# Accumulator_HotDog_v2.net
KiCad netlist of a schematic drawn in Altium Designer
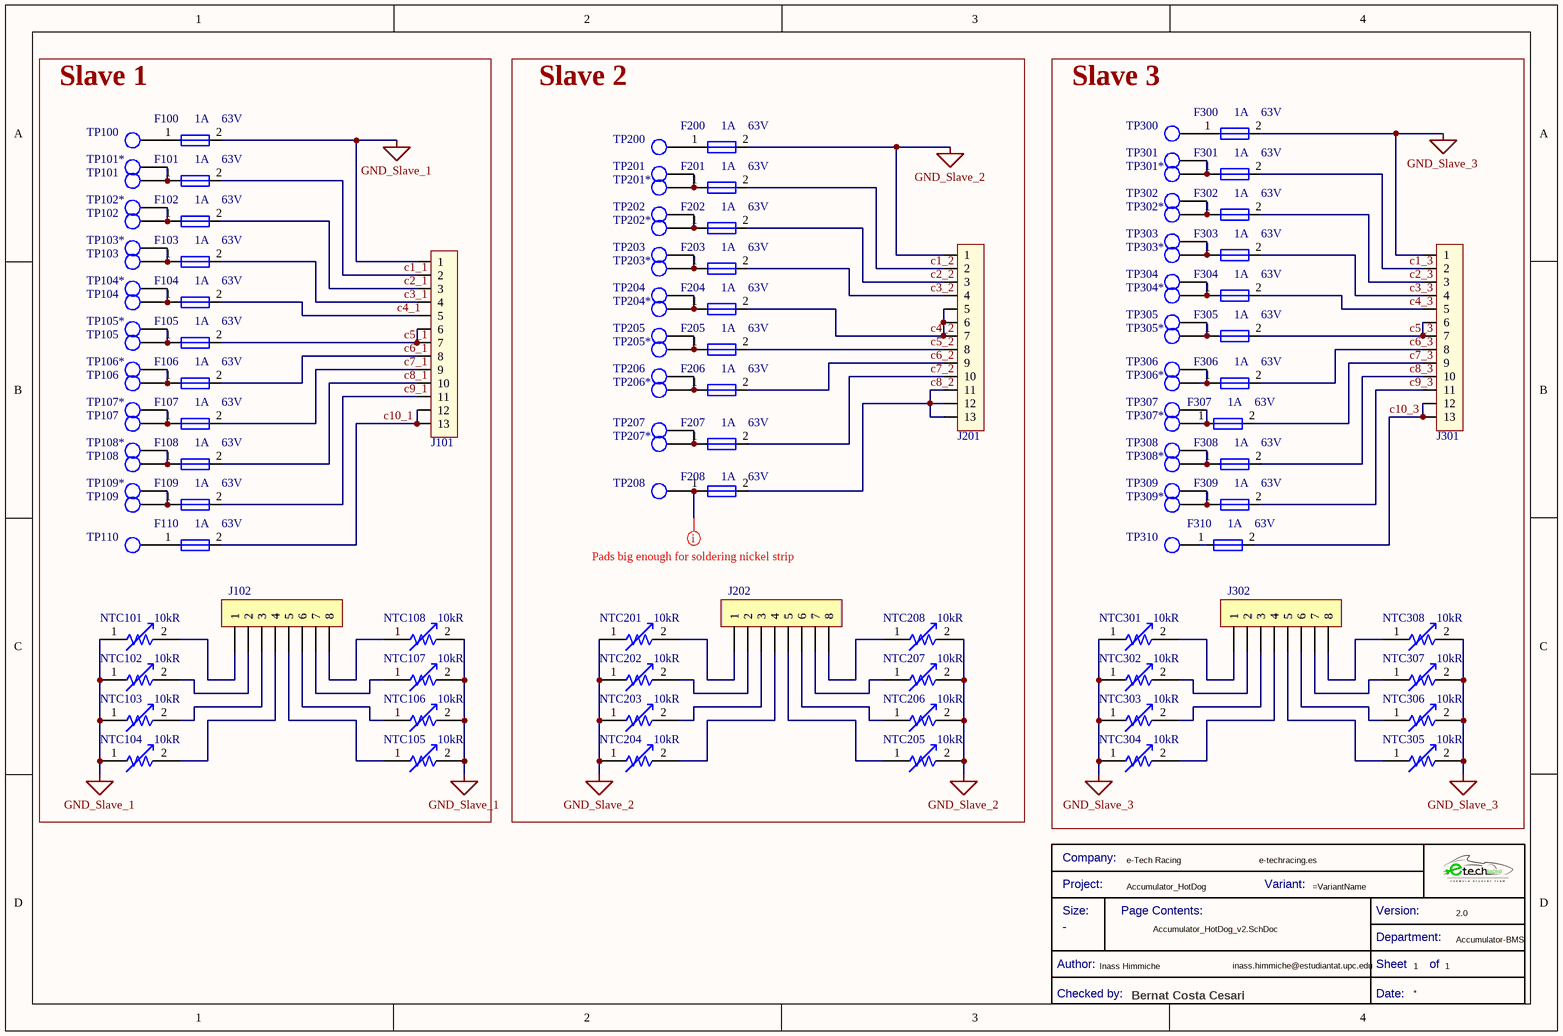
[diagram p0: Accumulator_HotDog_v2.SchDoc]

(export (version "E")
  (design (tool "Eeschema 10.0.6"))
  (components
    (comp (ref "*")
      (value "Title Block_template")
      (description "Standard Title Block")
      (fields (field (name "SIZE") "-"))
      (libsource (lib "e-Tech_Racing") (part "Title Block_template"))
    )
    (comp (ref "F100")
      (value "0437001.WRA")
      (footprint "Fuse_1206")
      (description "Fuse Chip Fast Acting 1A 63V SMD Solder Pad 1206 Ceramic T/R Automotive")
      (fields
        (field (name "MANUFACTURER") "Littelfuse")
        (field (name "CURRENT RATING") "1A")
        (field (name "VOLTAGE RATING (DC)") "63V")
      )
      (libsource (lib "Filter components") (part "Fuse_1A_63V_1206"))
    )
    (comp (ref "F101")
      (value "0437001.WRA")
      (footprint "Fuse_1206")
      (description "Fuse Chip Fast Acting 1A 63V SMD Solder Pad 1206 Ceramic T/R Automotive")
      (fields
        (field (name "MANUFACTURER") "Littelfuse")
        (field (name "CURRENT RATING") "1A")
        (field (name "VOLTAGE RATING (DC)") "63V")
      )
      (libsource (lib "Filter components") (part "Fuse_1A_63V_1206"))
    )
    (comp (ref "F102")
      (value "0437001.WRA")
      (footprint "Fuse_1206")
      (description "Fuse Chip Fast Acting 1A 63V SMD Solder Pad 1206 Ceramic T/R Automotive")
      (fields
        (field (name "MANUFACTURER") "Littelfuse")
        (field (name "CURRENT RATING") "1A")
        (field (name "VOLTAGE RATING (DC)") "63V")
      )
      (libsource (lib "Filter components") (part "Fuse_1A_63V_1206"))
    )
    (comp (ref "F103")
      (value "0437001.WRA")
      (footprint "Fuse_1206")
      (description "Fuse Chip Fast Acting 1A 63V SMD Solder Pad 1206 Ceramic T/R Automotive")
      (fields
        (field (name "MANUFACTURER") "Littelfuse")
        (field (name "CURRENT RATING") "1A")
        (field (name "VOLTAGE RATING (DC)") "63V")
      )
      (libsource (lib "Filter components") (part "Fuse_1A_63V_1206"))
    )
    (comp (ref "F104")
      (value "0437001.WRA")
      (footprint "Fuse_1206")
      (description "Fuse Chip Fast Acting 1A 63V SMD Solder Pad 1206 Ceramic T/R Automotive")
      (fields
        (field (name "MANUFACTURER") "Littelfuse")
        (field (name "CURRENT RATING") "1A")
        (field (name "VOLTAGE RATING (DC)") "63V")
      )
      (libsource (lib "Filter components") (part "Fuse_1A_63V_1206"))
    )
    (comp (ref "F105")
      (value "0437001.WRA")
      (footprint "Fuse_1206")
      (description "Fuse Chip Fast Acting 1A 63V SMD Solder Pad 1206 Ceramic T/R Automotive")
      (fields
        (field (name "MANUFACTURER") "Littelfuse")
        (field (name "CURRENT RATING") "1A")
        (field (name "VOLTAGE RATING (DC)") "63V")
      )
      (libsource (lib "Filter components") (part "Fuse_1A_63V_1206"))
    )
    (comp (ref "F106")
      (value "0437001.WRA")
      (footprint "Fuse_1206")
      (description "Fuse Chip Fast Acting 1A 63V SMD Solder Pad 1206 Ceramic T/R Automotive")
      (fields
        (field (name "MANUFACTURER") "Littelfuse")
        (field (name "CURRENT RATING") "1A")
        (field (name "VOLTAGE RATING (DC)") "63V")
      )
      (libsource (lib "Filter components") (part "Fuse_1A_63V_1206"))
    )
    (comp (ref "F107")
      (value "0437001.WRA")
      (footprint "Fuse_1206")
      (description "Fuse Chip Fast Acting 1A 63V SMD Solder Pad 1206 Ceramic T/R Automotive")
      (fields
        (field (name "MANUFACTURER") "Littelfuse")
        (field (name "CURRENT RATING") "1A")
        (field (name "VOLTAGE RATING (DC)") "63V")
      )
      (libsource (lib "Filter components") (part "Fuse_1A_63V_1206"))
    )
    (comp (ref "F108")
      (value "0437001.WRA")
      (footprint "Fuse_1206")
      (description "Fuse Chip Fast Acting 1A 63V SMD Solder Pad 1206 Ceramic T/R Automotive")
      (fields
        (field (name "MANUFACTURER") "Littelfuse")
        (field (name "CURRENT RATING") "1A")
        (field (name "VOLTAGE RATING (DC)") "63V")
      )
      (libsource (lib "Filter components") (part "Fuse_1A_63V_1206"))
    )
    (comp (ref "F109")
      (value "0437001.WRA")
      (footprint "Fuse_1206")
      (description "Fuse Chip Fast Acting 1A 63V SMD Solder Pad 1206 Ceramic T/R Automotive")
      (fields
        (field (name "MANUFACTURER") "Littelfuse")
        (field (name "CURRENT RATING") "1A")
        (field (name "VOLTAGE RATING (DC)") "63V")
      )
      (libsource (lib "Filter components") (part "Fuse_1A_63V_1206"))
    )
    (comp (ref "F110")
      (value "0437001.WRA")
      (footprint "Fuse_1206")
      (description "Fuse Chip Fast Acting 1A 63V SMD Solder Pad 1206 Ceramic T/R Automotive")
      (fields
        (field (name "MANUFACTURER") "Littelfuse")
        (field (name "CURRENT RATING") "1A")
        (field (name "VOLTAGE RATING (DC)") "63V")
      )
      (libsource (lib "Filter components") (part "Fuse_1A_63V_1206"))
    )
    (comp (ref "F200")
      (value "0437001.WRA")
      (footprint "Fuse_1206")
      (description "Fuse Chip Fast Acting 1A 63V SMD Solder Pad 1206 Ceramic T/R Automotive")
      (fields
        (field (name "MANUFACTURER") "Littelfuse")
        (field (name "CURRENT RATING") "1A")
        (field (name "VOLTAGE RATING (DC)") "63V")
      )
      (libsource (lib "Filter components") (part "Fuse_1A_63V_1206"))
    )
    (comp (ref "F201")
      (value "0437001.WRA")
      (footprint "Fuse_1206")
      (description "Fuse Chip Fast Acting 1A 63V SMD Solder Pad 1206 Ceramic T/R Automotive")
      (fields
        (field (name "MANUFACTURER") "Littelfuse")
        (field (name "CURRENT RATING") "1A")
        (field (name "VOLTAGE RATING (DC)") "63V")
      )
      (libsource (lib "Filter components") (part "Fuse_1A_63V_1206"))
    )
    (comp (ref "F202")
      (value "0437001.WRA")
      (footprint "Fuse_1206")
      (description "Fuse Chip Fast Acting 1A 63V SMD Solder Pad 1206 Ceramic T/R Automotive")
      (fields
        (field (name "MANUFACTURER") "Littelfuse")
        (field (name "CURRENT RATING") "1A")
        (field (name "VOLTAGE RATING (DC)") "63V")
      )
      (libsource (lib "Filter components") (part "Fuse_1A_63V_1206"))
    )
    (comp (ref "F203")
      (value "0437001.WRA")
      (footprint "Fuse_1206")
      (description "Fuse Chip Fast Acting 1A 63V SMD Solder Pad 1206 Ceramic T/R Automotive")
      (fields
        (field (name "MANUFACTURER") "Littelfuse")
        (field (name "CURRENT RATING") "1A")
        (field (name "VOLTAGE RATING (DC)") "63V")
      )
      (libsource (lib "Filter components") (part "Fuse_1A_63V_1206"))
    )
    (comp (ref "F204")
      (value "0437001.WRA")
      (footprint "Fuse_1206")
      (description "Fuse Chip Fast Acting 1A 63V SMD Solder Pad 1206 Ceramic T/R Automotive")
      (fields
        (field (name "MANUFACTURER") "Littelfuse")
        (field (name "CURRENT RATING") "1A")
        (field (name "VOLTAGE RATING (DC)") "63V")
      )
      (libsource (lib "Filter components") (part "Fuse_1A_63V_1206"))
    )
    (comp (ref "F205")
      (value "0437001.WRA")
      (footprint "Fuse_1206")
      (description "Fuse Chip Fast Acting 1A 63V SMD Solder Pad 1206 Ceramic T/R Automotive")
      (fields
        (field (name "MANUFACTURER") "Littelfuse")
        (field (name "CURRENT RATING") "1A")
        (field (name "VOLTAGE RATING (DC)") "63V")
      )
      (libsource (lib "Filter components") (part "Fuse_1A_63V_1206"))
    )
    (comp (ref "F206")
      (value "0437001.WRA")
      (footprint "Fuse_1206")
      (description "Fuse Chip Fast Acting 1A 63V SMD Solder Pad 1206 Ceramic T/R Automotive")
      (fields
        (field (name "MANUFACTURER") "Littelfuse")
        (field (name "CURRENT RATING") "1A")
        (field (name "VOLTAGE RATING (DC)") "63V")
      )
      (libsource (lib "Filter components") (part "Fuse_1A_63V_1206"))
    )
    (comp (ref "F207")
      (value "0437001.WRA")
      (footprint "Fuse_1206")
      (description "Fuse Chip Fast Acting 1A 63V SMD Solder Pad 1206 Ceramic T/R Automotive")
      (fields
        (field (name "MANUFACTURER") "Littelfuse")
        (field (name "CURRENT RATING") "1A")
        (field (name "VOLTAGE RATING (DC)") "63V")
      )
      (libsource (lib "Filter components") (part "Fuse_1A_63V_1206"))
    )
    (comp (ref "F208")
      (value "0437001.WRA")
      (footprint "Fuse_1206")
      (description "Fuse Chip Fast Acting 1A 63V SMD Solder Pad 1206 Ceramic T/R Automotive")
      (fields
        (field (name "MANUFACTURER") "Littelfuse")
        (field (name "CURRENT RATING") "1A")
        (field (name "VOLTAGE RATING (DC)") "63V")
      )
      (libsource (lib "Filter components") (part "Fuse_1A_63V_1206"))
    )
    (comp (ref "F300")
      (value "0437001.WRA")
      (footprint "Fuse_1206")
      (description "Fuse Chip Fast Acting 1A 63V SMD Solder Pad 1206 Ceramic T/R Automotive")
      (fields
        (field (name "MANUFACTURER") "Littelfuse")
        (field (name "CURRENT RATING") "1A")
        (field (name "VOLTAGE RATING (DC)") "63V")
      )
      (libsource (lib "Filter components") (part "Fuse_1A_63V_1206"))
    )
    (comp (ref "F301")
      (value "0437001.WRA")
      (footprint "Fuse_1206")
      (description "Fuse Chip Fast Acting 1A 63V SMD Solder Pad 1206 Ceramic T/R Automotive")
      (fields
        (field (name "MANUFACTURER") "Littelfuse")
        (field (name "CURRENT RATING") "1A")
        (field (name "VOLTAGE RATING (DC)") "63V")
      )
      (libsource (lib "Filter components") (part "Fuse_1A_63V_1206"))
    )
    (comp (ref "F302")
      (value "0437001.WRA")
      (footprint "Fuse_1206")
      (description "Fuse Chip Fast Acting 1A 63V SMD Solder Pad 1206 Ceramic T/R Automotive")
      (fields
        (field (name "MANUFACTURER") "Littelfuse")
        (field (name "CURRENT RATING") "1A")
        (field (name "VOLTAGE RATING (DC)") "63V")
      )
      (libsource (lib "Filter components") (part "Fuse_1A_63V_1206"))
    )
    (comp (ref "F303")
      (value "0437001.WRA")
      (footprint "Fuse_1206")
      (description "Fuse Chip Fast Acting 1A 63V SMD Solder Pad 1206 Ceramic T/R Automotive")
      (fields
        (field (name "MANUFACTURER") "Littelfuse")
        (field (name "CURRENT RATING") "1A")
        (field (name "VOLTAGE RATING (DC)") "63V")
      )
      (libsource (lib "Filter components") (part "Fuse_1A_63V_1206"))
    )
    (comp (ref "F304")
      (value "0437001.WRA")
      (footprint "Fuse_1206")
      (description "Fuse Chip Fast Acting 1A 63V SMD Solder Pad 1206 Ceramic T/R Automotive")
      (fields
        (field (name "MANUFACTURER") "Littelfuse")
        (field (name "CURRENT RATING") "1A")
        (field (name "VOLTAGE RATING (DC)") "63V")
      )
      (libsource (lib "Filter components") (part "Fuse_1A_63V_1206"))
    )
    (comp (ref "F305")
      (value "0437001.WRA")
      (footprint "Fuse_1206")
      (description "Fuse Chip Fast Acting 1A 63V SMD Solder Pad 1206 Ceramic T/R Automotive")
      (fields
        (field (name "MANUFACTURER") "Littelfuse")
        (field (name "CURRENT RATING") "1A")
        (field (name "VOLTAGE RATING (DC)") "63V")
      )
      (libsource (lib "Filter components") (part "Fuse_1A_63V_1206"))
    )
    (comp (ref "F306")
      (value "0437001.WRA")
      (footprint "Fuse_1206")
      (description "Fuse Chip Fast Acting 1A 63V SMD Solder Pad 1206 Ceramic T/R Automotive")
      (fields
        (field (name "MANUFACTURER") "Littelfuse")
        (field (name "CURRENT RATING") "1A")
        (field (name "VOLTAGE RATING (DC)") "63V")
      )
      (libsource (lib "Filter components") (part "Fuse_1A_63V_1206"))
    )
    (comp (ref "F307")
      (value "0437001.WRA")
      (footprint "Fuse_1206")
      (description "Fuse Chip Fast Acting 1A 63V SMD Solder Pad 1206 Ceramic T/R Automotive")
      (fields
        (field (name "MANUFACTURER") "Littelfuse")
        (field (name "CURRENT RATING") "1A")
        (field (name "VOLTAGE RATING (DC)") "63V")
      )
      (libsource (lib "Filter components") (part "Fuse_1A_63V_1206"))
    )
    (comp (ref "F308")
      (value "0437001.WRA")
      (footprint "Fuse_1206")
      (description "Fuse Chip Fast Acting 1A 63V SMD Solder Pad 1206 Ceramic T/R Automotive")
      (fields
        (field (name "MANUFACTURER") "Littelfuse")
        (field (name "CURRENT RATING") "1A")
        (field (name "VOLTAGE RATING (DC)") "63V")
      )
      (libsource (lib "Filter components") (part "Fuse_1A_63V_1206"))
    )
    (comp (ref "F309")
      (value "0437001.WRA")
      (footprint "Fuse_1206")
      (description "Fuse Chip Fast Acting 1A 63V SMD Solder Pad 1206 Ceramic T/R Automotive")
      (fields
        (field (name "MANUFACTURER") "Littelfuse")
        (field (name "CURRENT RATING") "1A")
        (field (name "VOLTAGE RATING (DC)") "63V")
      )
      (libsource (lib "Filter components") (part "Fuse_1A_63V_1206"))
    )
    (comp (ref "F310")
      (value "0437001.WRA")
      (footprint "Fuse_1206")
      (description "Fuse Chip Fast Acting 1A 63V SMD Solder Pad 1206 Ceramic T/R Automotive")
      (fields
        (field (name "MANUFACTURER") "Littelfuse")
        (field (name "CURRENT RATING") "1A")
        (field (name "VOLTAGE RATING (DC)") "63V")
      )
      (libsource (lib "Filter components") (part "Fuse_1A_63V_1206"))
    )
    (comp (ref "J101")
      (value "WR-PHD 13 socket header")
      (footprint "61301311821")
      (description "13 pin Socket Header 61301311821")
      (libsource (lib "Electromechanical") (part "J_WR-PHD 13pin Socket Header"))
    )
    (comp (ref "J102")
      (value "J_WR-PHD 8pin Socket Header")
      (footprint "61300811821")
      (description "8pin Socket Header 2.54 mm")
      (libsource (lib "Electromechanical") (part "J_WR-PHD 8pin Socket Header"))
    )
    (comp (ref "J201")
      (value "WR-PHD 13 socket header")
      (footprint "61301311821")
      (description "13 pin Socket Header 61301311821")
      (libsource (lib "Electromechanical") (part "J_WR-PHD 13pin Socket Header"))
    )
    (comp (ref "J202")
      (value "J_WR-PHD 8pin Socket Header")
      (footprint "61300811821")
      (description "8pin Socket Header 2.54 mm")
      (libsource (lib "Electromechanical") (part "J_WR-PHD 8pin Socket Header"))
    )
    (comp (ref "J301")
      (value "WR-PHD 13 socket header")
      (footprint "61301311821")
      (description "13 pin Socket Header 61301311821")
      (libsource (lib "Electromechanical") (part "J_WR-PHD 13pin Socket Header"))
    )
    (comp (ref "J302")
      (value "J_WR-PHD 8pin Socket Header")
      (footprint "61300811821")
      (description "8pin Socket Header 2.54 mm")
      (libsource (lib "Electromechanical") (part "J_WR-PHD 8pin Socket Header"))
    )
    (comp (ref "NTC101")
      (value "NXRT15XV103FA1B040")
      (footprint "NTC_NXRT15XV103FA1B040")
      (description "NXR Series 10 kOhm 3900 K ±1% Bead NTC Thermistor Sensor")
      (fields (field (name "TOLERANCE") "1%") (field (name "RESISTANCE") "10kR"))
      (libsource (lib "Sensors") (part "NTC_NXRT15XV103FA1B040"))
    )
    (comp (ref "NTC102")
      (value "NXRT15XV103FA1B040")
      (footprint "NTC_NXRT15XV103FA1B040")
      (description "NXR Series 10 kOhm 3900 K ±1% Bead NTC Thermistor Sensor")
      (fields (field (name "TOLERANCE") "1%") (field (name "RESISTANCE") "10kR"))
      (libsource (lib "Sensors") (part "NTC_NXRT15XV103FA1B040"))
    )
    (comp (ref "NTC103")
      (value "NXRT15XV103FA1B040")
      (footprint "NTC_NXRT15XV103FA1B040")
      (description "NXR Series 10 kOhm 3900 K ±1% Bead NTC Thermistor Sensor")
      (fields (field (name "TOLERANCE") "1%") (field (name "RESISTANCE") "10kR"))
      (libsource (lib "Sensors") (part "NTC_NXRT15XV103FA1B040"))
    )
    (comp (ref "NTC104")
      (value "NXRT15XV103FA1B040")
      (footprint "NTC_NXRT15XV103FA1B040")
      (description "NXR Series 10 kOhm 3900 K ±1% Bead NTC Thermistor Sensor")
      (fields (field (name "TOLERANCE") "1%") (field (name "RESISTANCE") "10kR"))
      (libsource (lib "Sensors") (part "NTC_NXRT15XV103FA1B040"))
    )
    (comp (ref "NTC105")
      (value "NXRT15XV103FA1B040")
      (footprint "NTC_NXRT15XV103FA1B040")
      (description "NXR Series 10 kOhm 3900 K ±1% Bead NTC Thermistor Sensor")
      (fields (field (name "TOLERANCE") "1%") (field (name "RESISTANCE") "10kR"))
      (libsource (lib "Sensors") (part "NTC_NXRT15XV103FA1B040"))
    )
    (comp (ref "NTC106")
      (value "NXRT15XV103FA1B040")
      (footprint "NTC_NXRT15XV103FA1B040")
      (description "NXR Series 10 kOhm 3900 K ±1% Bead NTC Thermistor Sensor")
      (fields (field (name "TOLERANCE") "1%") (field (name "RESISTANCE") "10kR"))
      (libsource (lib "Sensors") (part "NTC_NXRT15XV103FA1B040"))
    )
    (comp (ref "NTC107")
      (value "NXRT15XV103FA1B040")
      (footprint "NTC_NXRT15XV103FA1B040")
      (description "NXR Series 10 kOhm 3900 K ±1% Bead NTC Thermistor Sensor")
      (fields (field (name "TOLERANCE") "1%") (field (name "RESISTANCE") "10kR"))
      (libsource (lib "Sensors") (part "NTC_NXRT15XV103FA1B040"))
    )
    (comp (ref "NTC108")
      (value "NXRT15XV103FA1B040")
      (footprint "NTC_NXRT15XV103FA1B040")
      (description "NXR Series 10 kOhm 3900 K ±1% Bead NTC Thermistor Sensor")
      (fields (field (name "TOLERANCE") "1%") (field (name "RESISTANCE") "10kR"))
      (libsource (lib "Sensors") (part "NTC_NXRT15XV103FA1B040"))
    )
    (comp (ref "NTC201")
      (value "NXRT15XV103FA1B040")
      (footprint "NTC_NXRT15XV103FA1B040")
      (description "NXR Series 10 kOhm 3900 K ±1% Bead NTC Thermistor Sensor")
      (fields (field (name "TOLERANCE") "1%") (field (name "RESISTANCE") "10kR"))
      (libsource (lib "Sensors") (part "NTC_NXRT15XV103FA1B040"))
    )
    (comp (ref "NTC202")
      (value "NXRT15XV103FA1B040")
      (footprint "NTC_NXRT15XV103FA1B040")
      (description "NXR Series 10 kOhm 3900 K ±1% Bead NTC Thermistor Sensor")
      (fields (field (name "TOLERANCE") "1%") (field (name "RESISTANCE") "10kR"))
      (libsource (lib "Sensors") (part "NTC_NXRT15XV103FA1B040"))
    )
    (comp (ref "NTC203")
      (value "NXRT15XV103FA1B040")
      (footprint "NTC_NXRT15XV103FA1B040")
      (description "NXR Series 10 kOhm 3900 K ±1% Bead NTC Thermistor Sensor")
      (fields (field (name "TOLERANCE") "1%") (field (name "RESISTANCE") "10kR"))
      (libsource (lib "Sensors") (part "NTC_NXRT15XV103FA1B040"))
    )
    (comp (ref "NTC204")
      (value "NXRT15XV103FA1B040")
      (footprint "NTC_NXRT15XV103FA1B040")
      (description "NXR Series 10 kOhm 3900 K ±1% Bead NTC Thermistor Sensor")
      (fields (field (name "TOLERANCE") "1%") (field (name "RESISTANCE") "10kR"))
      (libsource (lib "Sensors") (part "NTC_NXRT15XV103FA1B040"))
    )
    (comp (ref "NTC205")
      (value "NXRT15XV103FA1B040")
      (footprint "NTC_NXRT15XV103FA1B040")
      (description "NXR Series 10 kOhm 3900 K ±1% Bead NTC Thermistor Sensor")
      (fields (field (name "TOLERANCE") "1%") (field (name "RESISTANCE") "10kR"))
      (libsource (lib "Sensors") (part "NTC_NXRT15XV103FA1B040"))
    )
    (comp (ref "NTC206")
      (value "NXRT15XV103FA1B040")
      (footprint "NTC_NXRT15XV103FA1B040")
      (description "NXR Series 10 kOhm 3900 K ±1% Bead NTC Thermistor Sensor")
      (fields (field (name "TOLERANCE") "1%") (field (name "RESISTANCE") "10kR"))
      (libsource (lib "Sensors") (part "NTC_NXRT15XV103FA1B040"))
    )
    (comp (ref "NTC207")
      (value "NXRT15XV103FA1B040")
      (footprint "NTC_NXRT15XV103FA1B040")
      (description "NXR Series 10 kOhm 3900 K ±1% Bead NTC Thermistor Sensor")
      (fields (field (name "TOLERANCE") "1%") (field (name "RESISTANCE") "10kR"))
      (libsource (lib "Sensors") (part "NTC_NXRT15XV103FA1B040"))
    )
    (comp (ref "NTC208")
      (value "NXRT15XV103FA1B040")
      (footprint "NTC_NXRT15XV103FA1B040")
      (description "NXR Series 10 kOhm 3900 K ±1% Bead NTC Thermistor Sensor")
      (fields (field (name "TOLERANCE") "1%") (field (name "RESISTANCE") "10kR"))
      (libsource (lib "Sensors") (part "NTC_NXRT15XV103FA1B040"))
    )
    (comp (ref "NTC301")
      (value "NXRT15XV103FA1B040")
      (footprint "NTC_NXRT15XV103FA1B040")
      (description "NXR Series 10 kOhm 3900 K ±1% Bead NTC Thermistor Sensor")
      (fields (field (name "TOLERANCE") "1%") (field (name "RESISTANCE") "10kR"))
      (libsource (lib "Sensors") (part "NTC_NXRT15XV103FA1B040"))
    )
    (comp (ref "NTC302")
      (value "NXRT15XV103FA1B040")
      (footprint "NTC_NXRT15XV103FA1B040")
      (description "NXR Series 10 kOhm 3900 K ±1% Bead NTC Thermistor Sensor")
      (fields (field (name "TOLERANCE") "1%") (field (name "RESISTANCE") "10kR"))
      (libsource (lib "Sensors") (part "NTC_NXRT15XV103FA1B040"))
    )
    (comp (ref "NTC303")
      (value "NXRT15XV103FA1B040")
      (footprint "NTC_NXRT15XV103FA1B040")
      (description "NXR Series 10 kOhm 3900 K ±1% Bead NTC Thermistor Sensor")
      (fields (field (name "TOLERANCE") "1%") (field (name "RESISTANCE") "10kR"))
      (libsource (lib "Sensors") (part "NTC_NXRT15XV103FA1B040"))
    )
    (comp (ref "NTC304")
      (value "NXRT15XV103FA1B040")
      (footprint "NTC_NXRT15XV103FA1B040")
      (description "NXR Series 10 kOhm 3900 K ±1% Bead NTC Thermistor Sensor")
      (fields (field (name "TOLERANCE") "1%") (field (name "RESISTANCE") "10kR"))
      (libsource (lib "Sensors") (part "NTC_NXRT15XV103FA1B040"))
    )
    (comp (ref "NTC305")
      (value "NXRT15XV103FA1B040")
      (footprint "NTC_NXRT15XV103FA1B040")
      (description "NXR Series 10 kOhm 3900 K ±1% Bead NTC Thermistor Sensor")
      (fields (field (name "TOLERANCE") "1%") (field (name "RESISTANCE") "10kR"))
      (libsource (lib "Sensors") (part "NTC_NXRT15XV103FA1B040"))
    )
    (comp (ref "NTC306")
      (value "NXRT15XV103FA1B040")
      (footprint "NTC_NXRT15XV103FA1B040")
      (description "NXR Series 10 kOhm 3900 K ±1% Bead NTC Thermistor Sensor")
      (fields (field (name "TOLERANCE") "1%") (field (name "RESISTANCE") "10kR"))
      (libsource (lib "Sensors") (part "NTC_NXRT15XV103FA1B040"))
    )
    (comp (ref "NTC307")
      (value "NXRT15XV103FA1B040")
      (footprint "NTC_NXRT15XV103FA1B040")
      (description "NXR Series 10 kOhm 3900 K ±1% Bead NTC Thermistor Sensor")
      (fields (field (name "TOLERANCE") "1%") (field (name "RESISTANCE") "10kR"))
      (libsource (lib "Sensors") (part "NTC_NXRT15XV103FA1B040"))
    )
    (comp (ref "NTC308")
      (value "NXRT15XV103FA1B040")
      (footprint "NTC_NXRT15XV103FA1B040")
      (description "NXR Series 10 kOhm 3900 K ±1% Bead NTC Thermistor Sensor")
      (fields (field (name "TOLERANCE") "1%") (field (name "RESISTANCE") "10kR"))
      (libsource (lib "Sensors") (part "NTC_NXRT15XV103FA1B040"))
    )
    (comp (ref "TP100")
      (value "TestPoint")
      (footprint "TestPoint")
      (description "Test Point 1x1 mm")
      (libsource (lib "e-Tech_Racing") (part "TestPoint"))
    )
    (comp (ref "TP101")
      (value "TestPoint")
      (footprint "TestPoint")
      (description "Test Point 1x1 mm")
      (libsource (lib "e-Tech_Racing") (part "TestPoint"))
    )
    (comp (ref "TP101*")
      (value "TestPoint")
      (footprint "TestPoint")
      (description "Test Point 1x1 mm")
      (libsource (lib "e-Tech_Racing") (part "TestPoint"))
    )
    (comp (ref "TP102")
      (value "TestPoint")
      (footprint "TestPoint")
      (description "Test Point 1x1 mm")
      (libsource (lib "e-Tech_Racing") (part "TestPoint"))
    )
    (comp (ref "TP102*")
      (value "TestPoint")
      (footprint "TestPoint")
      (description "Test Point 1x1 mm")
      (libsource (lib "e-Tech_Racing") (part "TestPoint"))
    )
    (comp (ref "TP103")
      (value "TestPoint")
      (footprint "TestPoint")
      (description "Test Point 1x1 mm")
      (libsource (lib "e-Tech_Racing") (part "TestPoint"))
    )
    (comp (ref "TP103*")
      (value "TestPoint")
      (footprint "TestPoint")
      (description "Test Point 1x1 mm")
      (libsource (lib "e-Tech_Racing") (part "TestPoint"))
    )
    (comp (ref "TP104")
      (value "TestPoint")
      (footprint "TestPoint")
      (description "Test Point 1x1 mm")
      (libsource (lib "e-Tech_Racing") (part "TestPoint"))
    )
    (comp (ref "TP104*")
      (value "TestPoint")
      (footprint "TestPoint")
      (description "Test Point 1x1 mm")
      (libsource (lib "e-Tech_Racing") (part "TestPoint"))
    )
    (comp (ref "TP105")
      (value "TestPoint")
      (footprint "TestPoint")
      (description "Test Point 1x1 mm")
      (libsource (lib "e-Tech_Racing") (part "TestPoint"))
    )
    (comp (ref "TP105*")
      (value "TestPoint")
      (footprint "TestPoint")
      (description "Test Point 1x1 mm")
      (libsource (lib "e-Tech_Racing") (part "TestPoint"))
    )
    (comp (ref "TP106")
      (value "TestPoint")
      (footprint "TestPoint")
      (description "Test Point 1x1 mm")
      (libsource (lib "e-Tech_Racing") (part "TestPoint"))
    )
    (comp (ref "TP106*")
      (value "TestPoint")
      (footprint "TestPoint")
      (description "Test Point 1x1 mm")
      (libsource (lib "e-Tech_Racing") (part "TestPoint"))
    )
    (comp (ref "TP107")
      (value "TestPoint")
      (footprint "TestPoint")
      (description "Test Point 1x1 mm")
      (libsource (lib "e-Tech_Racing") (part "TestPoint"))
    )
    (comp (ref "TP107*")
      (value "TestPoint")
      (footprint "TestPoint")
      (description "Test Point 1x1 mm")
      (libsource (lib "e-Tech_Racing") (part "TestPoint"))
    )
    (comp (ref "TP108")
      (value "TestPoint")
      (footprint "TestPoint")
      (description "Test Point 1x1 mm")
      (libsource (lib "e-Tech_Racing") (part "TestPoint"))
    )
    (comp (ref "TP108*")
      (value "TestPoint")
      (footprint "TestPoint")
      (description "Test Point 1x1 mm")
      (libsource (lib "e-Tech_Racing") (part "TestPoint"))
    )
    (comp (ref "TP109")
      (value "TestPoint")
      (footprint "TestPoint")
      (description "Test Point 1x1 mm")
      (libsource (lib "e-Tech_Racing") (part "TestPoint"))
    )
    (comp (ref "TP109*")
      (value "TestPoint")
      (footprint "TestPoint")
      (description "Test Point 1x1 mm")
      (libsource (lib "e-Tech_Racing") (part "TestPoint"))
    )
    (comp (ref "TP110")
      (value "TestPoint")
      (footprint "TestPoint")
      (description "Test Point 1x1 mm")
      (libsource (lib "e-Tech_Racing") (part "TestPoint"))
    )
    (comp (ref "TP200")
      (value "TestPoint")
      (footprint "TestPoint")
      (description "Test Point 1x1 mm")
      (libsource (lib "e-Tech_Racing") (part "TestPoint"))
    )
    (comp (ref "TP201")
      (value "TestPoint")
      (footprint "TestPoint")
      (description "Test Point 1x1 mm")
      (libsource (lib "e-Tech_Racing") (part "TestPoint"))
    )
    (comp (ref "TP201*")
      (value "TestPoint")
      (footprint "TestPoint")
      (description "Test Point 1x1 mm")
      (libsource (lib "e-Tech_Racing") (part "TestPoint"))
    )
    (comp (ref "TP202")
      (value "TestPoint")
      (footprint "TestPoint")
      (description "Test Point 1x1 mm")
      (libsource (lib "e-Tech_Racing") (part "TestPoint"))
    )
    (comp (ref "TP202*")
      (value "TestPoint")
      (footprint "TestPoint")
      (description "Test Point 1x1 mm")
      (libsource (lib "e-Tech_Racing") (part "TestPoint"))
    )
    (comp (ref "TP203")
      (value "TestPoint")
      (footprint "TestPoint")
      (description "Test Point 1x1 mm")
      (libsource (lib "e-Tech_Racing") (part "TestPoint"))
    )
    (comp (ref "TP203*")
      (value "TestPoint")
      (footprint "TestPoint")
      (description "Test Point 1x1 mm")
      (libsource (lib "e-Tech_Racing") (part "TestPoint"))
    )
    (comp (ref "TP204")
      (value "TestPoint")
      (footprint "TestPoint")
      (description "Test Point 1x1 mm")
      (libsource (lib "e-Tech_Racing") (part "TestPoint"))
    )
    (comp (ref "TP204*")
      (value "TestPoint")
      (footprint "TestPoint")
      (description "Test Point 1x1 mm")
      (libsource (lib "e-Tech_Racing") (part "TestPoint"))
    )
    (comp (ref "TP205")
      (value "TestPoint")
      (footprint "TestPoint")
      (description "Test Point 1x1 mm")
      (libsource (lib "e-Tech_Racing") (part "TestPoint"))
    )
    (comp (ref "TP205*")
      (value "TestPoint")
      (footprint "TestPoint")
      (description "Test Point 1x1 mm")
      (libsource (lib "e-Tech_Racing") (part "TestPoint"))
    )
    (comp (ref "TP206")
      (value "TestPoint")
      (footprint "TestPoint")
      (description "Test Point 1x1 mm")
      (libsource (lib "e-Tech_Racing") (part "TestPoint"))
    )
    (comp (ref "TP206*")
      (value "TestPoint")
      (footprint "TestPoint")
      (description "Test Point 1x1 mm")
      (libsource (lib "e-Tech_Racing") (part "TestPoint"))
    )
    (comp (ref "TP207")
      (value "TestPoint")
      (footprint "TestPoint")
      (description "Test Point 1x1 mm")
      (libsource (lib "e-Tech_Racing") (part "TestPoint"))
    )
    (comp (ref "TP207*")
      (value "TestPoint")
      (footprint "TestPoint")
      (description "Test Point 1x1 mm")
      (libsource (lib "e-Tech_Racing") (part "TestPoint"))
    )
    (comp (ref "TP208")
      (value "TestPoint")
      (footprint "TestPoint")
      (description "Test Point 1x1 mm")
      (libsource (lib "e-Tech_Racing") (part "TestPoint"))
    )
    (comp (ref "TP300")
      (value "TestPoint")
      (footprint "TestPoint")
      (description "Test Point 1x1 mm")
      (libsource (lib "e-Tech_Racing") (part "TestPoint"))
    )
    (comp (ref "TP301")
      (value "TestPoint")
      (footprint "TestPoint")
      (description "Test Point 1x1 mm")
      (libsource (lib "e-Tech_Racing") (part "TestPoint"))
    )
    (comp (ref "TP301*")
      (value "TestPoint")
      (footprint "TestPoint")
      (description "Test Point 1x1 mm")
      (libsource (lib "e-Tech_Racing") (part "TestPoint"))
    )
    (comp (ref "TP302")
      (value "TestPoint")
      (footprint "TestPoint")
      (description "Test Point 1x1 mm")
      (libsource (lib "e-Tech_Racing") (part "TestPoint"))
    )
    (comp (ref "TP302*")
      (value "TestPoint")
      (footprint "TestPoint")
      (description "Test Point 1x1 mm")
      (libsource (lib "e-Tech_Racing") (part "TestPoint"))
    )
    (comp (ref "TP303")
      (value "TestPoint")
      (footprint "TestPoint")
      (description "Test Point 1x1 mm")
      (libsource (lib "e-Tech_Racing") (part "TestPoint"))
    )
    (comp (ref "TP303*")
      (value "TestPoint")
      (footprint "TestPoint")
      (description "Test Point 1x1 mm")
      (libsource (lib "e-Tech_Racing") (part "TestPoint"))
    )
    (comp (ref "TP304")
      (value "TestPoint")
      (footprint "TestPoint")
      (description "Test Point 1x1 mm")
      (libsource (lib "e-Tech_Racing") (part "TestPoint"))
    )
    (comp (ref "TP304*")
      (value "TestPoint")
      (footprint "TestPoint")
      (description "Test Point 1x1 mm")
      (libsource (lib "e-Tech_Racing") (part "TestPoint"))
    )
    (comp (ref "TP305")
      (value "TestPoint")
      (footprint "TestPoint")
      (description "Test Point 1x1 mm")
      (libsource (lib "e-Tech_Racing") (part "TestPoint"))
    )
    (comp (ref "TP305*")
      (value "TestPoint")
      (footprint "TestPoint")
      (description "Test Point 1x1 mm")
      (libsource (lib "e-Tech_Racing") (part "TestPoint"))
    )
    (comp (ref "TP306")
      (value "TestPoint")
      (footprint "TestPoint")
      (description "Test Point 1x1 mm")
      (libsource (lib "e-Tech_Racing") (part "TestPoint"))
    )
    (comp (ref "TP306*")
      (value "TestPoint")
      (footprint "TestPoint")
      (description "Test Point 1x1 mm")
      (libsource (lib "e-Tech_Racing") (part "TestPoint"))
    )
    (comp (ref "TP307")
      (value "TestPoint")
      (footprint "TestPoint")
      (description "Test Point 1x1 mm")
      (libsource (lib "e-Tech_Racing") (part "TestPoint"))
    )
    (comp (ref "TP307*")
      (value "TestPoint")
      (footprint "TestPoint")
      (description "Test Point 1x1 mm")
      (libsource (lib "e-Tech_Racing") (part "TestPoint"))
    )
    (comp (ref "TP308")
      (value "TestPoint")
      (footprint "TestPoint")
      (description "Test Point 1x1 mm")
      (libsource (lib "e-Tech_Racing") (part "TestPoint"))
    )
    (comp (ref "TP308*")
      (value "TestPoint")
      (footprint "TestPoint")
      (description "Test Point 1x1 mm")
      (libsource (lib "e-Tech_Racing") (part "TestPoint"))
    )
    (comp (ref "TP309")
      (value "TestPoint")
      (footprint "TestPoint")
      (description "Test Point 1x1 mm")
      (libsource (lib "e-Tech_Racing") (part "TestPoint"))
    )
    (comp (ref "TP309*")
      (value "TestPoint")
      (footprint "TestPoint")
      (description "Test Point 1x1 mm")
      (libsource (lib "e-Tech_Racing") (part "TestPoint"))
    )
    (comp (ref "TP310")
      (value "TestPoint")
      (footprint "TestPoint")
      (description "Test Point 1x1 mm")
      (libsource (lib "e-Tech_Racing") (part "TestPoint"))
    )
  )
  (nets
    (net (code "1") (name "/c1_1") (class "Default")
      (node (ref "F101") (pin "2") (pinfunction "2_2") (pintype "passive"))
      (node (ref "J101") (pin "2") (pinfunction "2_2") (pintype "passive"))
    )
    (net (code "2") (name "/c1_2") (class "Default")
      (node (ref "F201") (pin "2") (pinfunction "2_2") (pintype "passive"))
      (node (ref "J201") (pin "2") (pinfunction "2_2") (pintype "passive"))
    )
    (net (code "3") (name "/c1_3") (class "Default")
      (node (ref "F301") (pin "2") (pinfunction "2_2") (pintype "passive"))
      (node (ref "J301") (pin "2") (pinfunction "2_2") (pintype "passive"))
    )
    (net (code "4") (name "/c2_1") (class "Default")
      (node (ref "F102") (pin "2") (pinfunction "2_2") (pintype "passive"))
      (node (ref "J101") (pin "3") (pinfunction "3_3") (pintype "passive"))
    )
    (net (code "5") (name "/c2_2") (class "Default")
      (node (ref "F202") (pin "2") (pinfunction "2_2") (pintype "passive"))
      (node (ref "J201") (pin "3") (pinfunction "3_3") (pintype "passive"))
    )
    (net (code "6") (name "/c2_3") (class "Default")
      (node (ref "F302") (pin "2") (pinfunction "2_2") (pintype "passive"))
      (node (ref "J301") (pin "3") (pinfunction "3_3") (pintype "passive"))
    )
    (net (code "7") (name "/c3_1") (class "Default")
      (node (ref "F103") (pin "2") (pinfunction "2_2") (pintype "passive"))
      (node (ref "J101") (pin "4") (pinfunction "4_4") (pintype "passive"))
    )
    (net (code "8") (name "/c3_2") (class "Default")
      (node (ref "F203") (pin "2") (pinfunction "2_2") (pintype "passive"))
      (node (ref "J201") (pin "4") (pinfunction "4_4") (pintype "passive"))
    )
    (net (code "9") (name "/c3_3") (class "Default")
      (node (ref "F303") (pin "2") (pinfunction "2_2") (pintype "passive"))
      (node (ref "J301") (pin "4") (pinfunction "4_4") (pintype "passive"))
    )
    (net (code "10") (name "/c4_1") (class "Default")
      (node (ref "F104") (pin "2") (pinfunction "2_2") (pintype "passive"))
      (node (ref "J101") (pin "5") (pinfunction "5_5") (pintype "passive"))
    )
    (net (code "11") (name "/c4_2") (class "Default")
      (node (ref "F204") (pin "2") (pinfunction "2_2") (pintype "passive"))
      (node (ref "J201") (pin "5") (pinfunction "5_5") (pintype "passive"))
      (node (ref "J201") (pin "6") (pinfunction "6_6") (pintype "passive"))
      (node (ref "J201") (pin "7") (pinfunction "7_7") (pintype "passive"))
    )
    (net (code "12") (name "/c4_3") (class "Default")
      (node (ref "F304") (pin "2") (pinfunction "2_2") (pintype "passive"))
      (node (ref "J301") (pin "5") (pinfunction "5_5") (pintype "passive"))
    )
    (net (code "13") (name "/c5_1") (class "Default")
      (node (ref "F105") (pin "2") (pinfunction "2_2") (pintype "passive"))
      (node (ref "J101") (pin "6") (pinfunction "6_6") (pintype "passive"))
      (node (ref "J101") (pin "7") (pinfunction "7_7") (pintype "passive"))
    )
    (net (code "14") (name "/c5_2") (class "Default")
      (node (ref "F205") (pin "2") (pinfunction "2_2") (pintype "passive"))
      (node (ref "J201") (pin "8") (pinfunction "8_8") (pintype "passive"))
    )
    (net (code "15") (name "/c5_3") (class "Default")
      (node (ref "F305") (pin "2") (pinfunction "2_2") (pintype "passive"))
      (node (ref "J301") (pin "6") (pinfunction "6_6") (pintype "passive"))
      (node (ref "J301") (pin "7") (pinfunction "7_7") (pintype "passive"))
    )
    (net (code "16") (name "/c6_1") (class "Default")
      (node (ref "F106") (pin "2") (pinfunction "2_2") (pintype "passive"))
      (node (ref "J101") (pin "8") (pinfunction "8_8") (pintype "passive"))
    )
    (net (code "17") (name "/c6_2") (class "Default")
      (node (ref "F206") (pin "2") (pinfunction "2_2") (pintype "passive"))
      (node (ref "J201") (pin "9") (pinfunction "9_9") (pintype "passive"))
    )
    (net (code "18") (name "/c6_3") (class "Default")
      (node (ref "F306") (pin "2") (pinfunction "2_2") (pintype "passive"))
      (node (ref "J301") (pin "8") (pinfunction "8_8") (pintype "passive"))
    )
    (net (code "19") (name "/c7_1") (class "Default")
      (node (ref "F107") (pin "2") (pinfunction "2_2") (pintype "passive"))
      (node (ref "J101") (pin "9") (pinfunction "9_9") (pintype "passive"))
    )
    (net (code "20") (name "/c7_2") (class "Default")
      (node (ref "F207") (pin "2") (pinfunction "2_2") (pintype "passive"))
      (node (ref "J201") (pin "10") (pinfunction "10_10") (pintype "passive"))
    )
    (net (code "21") (name "/c7_3") (class "Default")
      (node (ref "F307") (pin "2") (pinfunction "2_2") (pintype "passive"))
      (node (ref "J301") (pin "9") (pinfunction "9_9") (pintype "passive"))
    )
    (net (code "22") (name "/c8_1") (class "Default")
      (node (ref "F108") (pin "2") (pinfunction "2_2") (pintype "passive"))
      (node (ref "J101") (pin "10") (pinfunction "10_10") (pintype "passive"))
    )
    (net (code "23") (name "/c8_2") (class "Default")
      (node (ref "F208") (pin "2") (pinfunction "2_2") (pintype "passive"))
      (node (ref "J201") (pin "11") (pinfunction "11_11") (pintype "passive"))
      (node (ref "J201") (pin "12") (pinfunction "12_12") (pintype "passive"))
      (node (ref "J201") (pin "13") (pinfunction "13_13") (pintype "passive"))
    )
    (net (code "24") (name "/c8_3") (class "Default")
      (node (ref "F308") (pin "2") (pinfunction "2_2") (pintype "passive"))
      (node (ref "J301") (pin "10") (pinfunction "10_10") (pintype "passive"))
    )
    (net (code "25") (name "/c9_1") (class "Default")
      (node (ref "F109") (pin "2") (pinfunction "2_2") (pintype "passive"))
      (node (ref "J101") (pin "11") (pinfunction "11_11") (pintype "passive"))
    )
    (net (code "26") (name "/c9_3") (class "Default")
      (node (ref "F309") (pin "2") (pinfunction "2_2") (pintype "passive"))
      (node (ref "J301") (pin "11") (pinfunction "11_11") (pintype "passive"))
    )
    (net (code "27") (name "/c10_1") (class "Default")
      (node (ref "F110") (pin "2") (pinfunction "2_2") (pintype "passive"))
      (node (ref "J101") (pin "12") (pinfunction "12_12") (pintype "passive"))
      (node (ref "J101") (pin "13") (pinfunction "13_13") (pintype "passive"))
    )
    (net (code "28") (name "/c10_3") (class "Default")
      (node (ref "F310") (pin "2") (pinfunction "2_2") (pintype "passive"))
      (node (ref "J301") (pin "12") (pinfunction "12_12") (pintype "passive"))
      (node (ref "J301") (pin "13") (pinfunction "13_13") (pintype "passive"))
    )
    (net (code "29") (name "GND_Slave_1") (class "Default")
      (node (ref "F100") (pin "2") (pinfunction "2_2") (pintype "passive"))
      (node (ref "J101") (pin "1") (pinfunction "1_1") (pintype "passive"))
      (node (ref "NTC101") (pin "1") (pinfunction "2_1") (pintype "passive"))
      (node (ref "NTC102") (pin "1") (pinfunction "2_1") (pintype "passive"))
      (node (ref "NTC103") (pin "1") (pinfunction "2_1") (pintype "passive"))
      (node (ref "NTC104") (pin "1") (pinfunction "2_1") (pintype "passive"))
      (node (ref "NTC105") (pin "2") (pinfunction "2_2") (pintype "passive"))
      (node (ref "NTC106") (pin "2") (pinfunction "2_2") (pintype "passive"))
      (node (ref "NTC107") (pin "2") (pinfunction "2_2") (pintype "passive"))
      (node (ref "NTC108") (pin "2") (pinfunction "2_2") (pintype "passive"))
    )
    (net (code "30") (name "GND_Slave_2") (class "Default")
      (node (ref "F200") (pin "2") (pinfunction "2_2") (pintype "passive"))
      (node (ref "J201") (pin "1") (pinfunction "1_1") (pintype "passive"))
      (node (ref "NTC201") (pin "1") (pinfunction "2_1") (pintype "passive"))
      (node (ref "NTC202") (pin "1") (pinfunction "2_1") (pintype "passive"))
      (node (ref "NTC203") (pin "1") (pinfunction "2_1") (pintype "passive"))
      (node (ref "NTC204") (pin "1") (pinfunction "2_1") (pintype "passive"))
      (node (ref "NTC205") (pin "2") (pinfunction "2_2") (pintype "passive"))
      (node (ref "NTC206") (pin "2") (pinfunction "2_2") (pintype "passive"))
      (node (ref "NTC207") (pin "2") (pinfunction "2_2") (pintype "passive"))
      (node (ref "NTC208") (pin "2") (pinfunction "2_2") (pintype "passive"))
    )
    (net (code "31") (name "GND_Slave_3") (class "Default")
      (node (ref "F300") (pin "2") (pinfunction "2_2") (pintype "passive"))
      (node (ref "J301") (pin "1") (pinfunction "1_1") (pintype "passive"))
      (node (ref "NTC301") (pin "1") (pinfunction "2_1") (pintype "passive"))
      (node (ref "NTC302") (pin "1") (pinfunction "2_1") (pintype "passive"))
      (node (ref "NTC303") (pin "1") (pinfunction "2_1") (pintype "passive"))
      (node (ref "NTC304") (pin "1") (pinfunction "2_1") (pintype "passive"))
      (node (ref "NTC305") (pin "2") (pinfunction "2_2") (pintype "passive"))
      (node (ref "NTC306") (pin "2") (pinfunction "2_2") (pintype "passive"))
      (node (ref "NTC307") (pin "2") (pinfunction "2_2") (pintype "passive"))
      (node (ref "NTC308") (pin "2") (pinfunction "2_2") (pintype "passive"))
    )
    (net (code "32") (name "Net-(F100-Pad1)") (class "Default")
      (node (ref "F100") (pin "1") (pinfunction "1_1") (pintype "passive"))
      (node (ref "TP100") (pin "1") (pinfunction "1_1") (pintype "passive"))
    )
    (net (code "33") (name "Net-(F101-Pad1)") (class "Default")
      (node (ref "F101") (pin "1") (pinfunction "1_1") (pintype "passive"))
      (node (ref "TP101") (pin "1") (pinfunction "1_1") (pintype "passive"))
      (node (ref "TP101*") (pin "1") (pinfunction "1_1") (pintype "passive"))
    )
    (net (code "34") (name "Net-(F102-Pad1)") (class "Default")
      (node (ref "F102") (pin "1") (pinfunction "1_1") (pintype "passive"))
      (node (ref "TP102") (pin "1") (pinfunction "1_1") (pintype "passive"))
      (node (ref "TP102*") (pin "1") (pinfunction "1_1") (pintype "passive"))
    )
    (net (code "35") (name "Net-(F103-Pad1)") (class "Default")
      (node (ref "F103") (pin "1") (pinfunction "1_1") (pintype "passive"))
      (node (ref "TP103") (pin "1") (pinfunction "1_1") (pintype "passive"))
      (node (ref "TP103*") (pin "1") (pinfunction "1_1") (pintype "passive"))
    )
    (net (code "36") (name "Net-(F104-Pad1)") (class "Default")
      (node (ref "F104") (pin "1") (pinfunction "1_1") (pintype "passive"))
      (node (ref "TP104") (pin "1") (pinfunction "1_1") (pintype "passive"))
      (node (ref "TP104*") (pin "1") (pinfunction "1_1") (pintype "passive"))
    )
    (net (code "37") (name "Net-(F105-Pad1)") (class "Default")
      (node (ref "F105") (pin "1") (pinfunction "1_1") (pintype "passive"))
      (node (ref "TP105") (pin "1") (pinfunction "1_1") (pintype "passive"))
      (node (ref "TP105*") (pin "1") (pinfunction "1_1") (pintype "passive"))
    )
    (net (code "38") (name "Net-(F106-Pad1)") (class "Default")
      (node (ref "F106") (pin "1") (pinfunction "1_1") (pintype "passive"))
      (node (ref "TP106") (pin "1") (pinfunction "1_1") (pintype "passive"))
      (node (ref "TP106*") (pin "1") (pinfunction "1_1") (pintype "passive"))
    )
    (net (code "39") (name "Net-(F107-Pad1)") (class "Default")
      (node (ref "F107") (pin "1") (pinfunction "1_1") (pintype "passive"))
      (node (ref "TP107") (pin "1") (pinfunction "1_1") (pintype "passive"))
      (node (ref "TP107*") (pin "1") (pinfunction "1_1") (pintype "passive"))
    )
    (net (code "40") (name "Net-(F108-Pad1)") (class "Default")
      (node (ref "F108") (pin "1") (pinfunction "1_1") (pintype "passive"))
      (node (ref "TP108") (pin "1") (pinfunction "1_1") (pintype "passive"))
      (node (ref "TP108*") (pin "1") (pinfunction "1_1") (pintype "passive"))
    )
    (net (code "41") (name "Net-(F109-Pad1)") (class "Default")
      (node (ref "F109") (pin "1") (pinfunction "1_1") (pintype "passive"))
      (node (ref "TP109") (pin "1") (pinfunction "1_1") (pintype "passive"))
      (node (ref "TP109*") (pin "1") (pinfunction "1_1") (pintype "passive"))
    )
    (net (code "42") (name "Net-(F110-Pad1)") (class "Default")
      (node (ref "F110") (pin "1") (pinfunction "1_1") (pintype "passive"))
      (node (ref "TP110") (pin "1") (pinfunction "1_1") (pintype "passive"))
    )
    (net (code "43") (name "Net-(F200-Pad1)") (class "Default")
      (node (ref "F200") (pin "1") (pinfunction "1_1") (pintype "passive"))
      (node (ref "TP200") (pin "1") (pinfunction "1_1") (pintype "passive"))
    )
    (net (code "44") (name "Net-(F201-Pad1)") (class "Default")
      (node (ref "F201") (pin "1") (pinfunction "1_1") (pintype "passive"))
      (node (ref "TP201") (pin "1") (pinfunction "1_1") (pintype "passive"))
      (node (ref "TP201*") (pin "1") (pinfunction "1_1") (pintype "passive"))
    )
    (net (code "45") (name "Net-(F202-Pad1)") (class "Default")
      (node (ref "F202") (pin "1") (pinfunction "1_1") (pintype "passive"))
      (node (ref "TP202") (pin "1") (pinfunction "1_1") (pintype "passive"))
      (node (ref "TP202*") (pin "1") (pinfunction "1_1") (pintype "passive"))
    )
    (net (code "46") (name "Net-(F203-Pad1)") (class "Default")
      (node (ref "F203") (pin "1") (pinfunction "1_1") (pintype "passive"))
      (node (ref "TP203") (pin "1") (pinfunction "1_1") (pintype "passive"))
      (node (ref "TP203*") (pin "1") (pinfunction "1_1") (pintype "passive"))
    )
    (net (code "47") (name "Net-(F204-Pad1)") (class "Default")
      (node (ref "F204") (pin "1") (pinfunction "1_1") (pintype "passive"))
      (node (ref "TP204") (pin "1") (pinfunction "1_1") (pintype "passive"))
      (node (ref "TP204*") (pin "1") (pinfunction "1_1") (pintype "passive"))
    )
    (net (code "48") (name "Net-(F205-Pad1)") (class "Default")
      (node (ref "F205") (pin "1") (pinfunction "1_1") (pintype "passive"))
      (node (ref "TP205") (pin "1") (pinfunction "1_1") (pintype "passive"))
      (node (ref "TP205*") (pin "1") (pinfunction "1_1") (pintype "passive"))
    )
    (net (code "49") (name "Net-(F206-Pad1)") (class "Default")
      (node (ref "F206") (pin "1") (pinfunction "1_1") (pintype "passive"))
      (node (ref "TP206") (pin "1") (pinfunction "1_1") (pintype "passive"))
      (node (ref "TP206*") (pin "1") (pinfunction "1_1") (pintype "passive"))
    )
    (net (code "50") (name "Net-(F207-Pad1)") (class "Default")
      (node (ref "F207") (pin "1") (pinfunction "1_1") (pintype "passive"))
      (node (ref "TP207") (pin "1") (pinfunction "1_1") (pintype "passive"))
      (node (ref "TP207*") (pin "1") (pinfunction "1_1") (pintype "passive"))
    )
    (net (code "51") (name "Net-(F208-Pad1)") (class "Default")
      (node (ref "F208") (pin "1") (pinfunction "1_1") (pintype "passive"))
      (node (ref "TP208") (pin "1") (pinfunction "1_1") (pintype "passive"))
    )
    (net (code "52") (name "Net-(F300-Pad1)") (class "Default")
      (node (ref "F300") (pin "1") (pinfunction "1_1") (pintype "passive"))
      (node (ref "TP300") (pin "1") (pinfunction "1_1") (pintype "passive"))
    )
    (net (code "53") (name "Net-(F301-Pad1)") (class "Default")
      (node (ref "F301") (pin "1") (pinfunction "1_1") (pintype "passive"))
      (node (ref "TP301") (pin "1") (pinfunction "1_1") (pintype "passive"))
      (node (ref "TP301*") (pin "1") (pinfunction "1_1") (pintype "passive"))
    )
    (net (code "54") (name "Net-(F302-Pad1)") (class "Default")
      (node (ref "F302") (pin "1") (pinfunction "1_1") (pintype "passive"))
      (node (ref "TP302") (pin "1") (pinfunction "1_1") (pintype "passive"))
      (node (ref "TP302*") (pin "1") (pinfunction "1_1") (pintype "passive"))
    )
    (net (code "55") (name "Net-(F303-Pad1)") (class "Default")
      (node (ref "F303") (pin "1") (pinfunction "1_1") (pintype "passive"))
      (node (ref "TP303") (pin "1") (pinfunction "1_1") (pintype "passive"))
      (node (ref "TP303*") (pin "1") (pinfunction "1_1") (pintype "passive"))
    )
    (net (code "56") (name "Net-(F304-Pad1)") (class "Default")
      (node (ref "F304") (pin "1") (pinfunction "1_1") (pintype "passive"))
      (node (ref "TP304") (pin "1") (pinfunction "1_1") (pintype "passive"))
      (node (ref "TP304*") (pin "1") (pinfunction "1_1") (pintype "passive"))
    )
    (net (code "57") (name "Net-(F305-Pad1)") (class "Default")
      (node (ref "F305") (pin "1") (pinfunction "1_1") (pintype "passive"))
      (node (ref "TP305") (pin "1") (pinfunction "1_1") (pintype "passive"))
      (node (ref "TP305*") (pin "1") (pinfunction "1_1") (pintype "passive"))
    )
    (net (code "58") (name "Net-(F306-Pad1)") (class "Default")
      (node (ref "F306") (pin "1") (pinfunction "1_1") (pintype "passive"))
      (node (ref "TP306") (pin "1") (pinfunction "1_1") (pintype "passive"))
      (node (ref "TP306*") (pin "1") (pinfunction "1_1") (pintype "passive"))
    )
    (net (code "59") (name "Net-(F307-Pad1)") (class "Default")
      (node (ref "F307") (pin "1") (pinfunction "1_1") (pintype "passive"))
      (node (ref "TP307") (pin "1") (pinfunction "1_1") (pintype "passive"))
      (node (ref "TP307*") (pin "1") (pinfunction "1_1") (pintype "passive"))
    )
    (net (code "60") (name "Net-(F308-Pad1)") (class "Default")
      (node (ref "F308") (pin "1") (pinfunction "1_1") (pintype "passive"))
      (node (ref "TP308") (pin "1") (pinfunction "1_1") (pintype "passive"))
      (node (ref "TP308*") (pin "1") (pinfunction "1_1") (pintype "passive"))
    )
    (net (code "61") (name "Net-(F309-Pad1)") (class "Default")
      (node (ref "F309") (pin "1") (pinfunction "1_1") (pintype "passive"))
      (node (ref "TP309") (pin "1") (pinfunction "1_1") (pintype "passive"))
      (node (ref "TP309*") (pin "1") (pinfunction "1_1") (pintype "passive"))
    )
    (net (code "62") (name "Net-(F310-Pad1)") (class "Default")
      (node (ref "F310") (pin "1") (pinfunction "1_1") (pintype "passive"))
      (node (ref "TP310") (pin "1") (pinfunction "1_1") (pintype "passive"))
    )
    (net (code "63") (name "Net-(J102-Pad1)") (class "Default")
      (node (ref "J102") (pin "1") (pinfunction "1_1") (pintype "passive"))
      (node (ref "NTC101") (pin "2") (pinfunction "2_2") (pintype "passive"))
    )
    (net (code "64") (name "Net-(J102-Pad2)") (class "Default")
      (node (ref "J102") (pin "2") (pinfunction "2_2") (pintype "passive"))
      (node (ref "NTC102") (pin "2") (pinfunction "2_2") (pintype "passive"))
    )
    (net (code "65") (name "Net-(J102-Pad3)") (class "Default")
      (node (ref "J102") (pin "3") (pinfunction "3_3") (pintype "passive"))
      (node (ref "NTC103") (pin "2") (pinfunction "2_2") (pintype "passive"))
    )
    (net (code "66") (name "Net-(J102-Pad4)") (class "Default")
      (node (ref "J102") (pin "4") (pinfunction "4_4") (pintype "passive"))
      (node (ref "NTC104") (pin "2") (pinfunction "2_2") (pintype "passive"))
    )
    (net (code "67") (name "Net-(J102-Pad5)") (class "Default")
      (node (ref "J102") (pin "5") (pinfunction "5_5") (pintype "passive"))
      (node (ref "NTC105") (pin "1") (pinfunction "2_1") (pintype "passive"))
    )
    (net (code "68") (name "Net-(J102-Pad6)") (class "Default")
      (node (ref "J102") (pin "6") (pinfunction "6_6") (pintype "passive"))
      (node (ref "NTC106") (pin "1") (pinfunction "2_1") (pintype "passive"))
    )
    (net (code "69") (name "Net-(J102-Pad7)") (class "Default")
      (node (ref "J102") (pin "7") (pinfunction "7_7") (pintype "passive"))
      (node (ref "NTC107") (pin "1") (pinfunction "2_1") (pintype "passive"))
    )
    (net (code "70") (name "Net-(J102-Pad8)") (class "Default")
      (node (ref "J102") (pin "8") (pinfunction "8_8") (pintype "passive"))
      (node (ref "NTC108") (pin "1") (pinfunction "2_1") (pintype "passive"))
    )
    (net (code "71") (name "Net-(J202-Pad1)") (class "Default")
      (node (ref "J202") (pin "1") (pinfunction "1_1") (pintype "passive"))
      (node (ref "NTC201") (pin "2") (pinfunction "2_2") (pintype "passive"))
    )
    (net (code "72") (name "Net-(J202-Pad2)") (class "Default")
      (node (ref "J202") (pin "2") (pinfunction "2_2") (pintype "passive"))
      (node (ref "NTC202") (pin "2") (pinfunction "2_2") (pintype "passive"))
    )
    (net (code "73") (name "Net-(J202-Pad3)") (class "Default")
      (node (ref "J202") (pin "3") (pinfunction "3_3") (pintype "passive"))
      (node (ref "NTC203") (pin "2") (pinfunction "2_2") (pintype "passive"))
    )
    (net (code "74") (name "Net-(J202-Pad4)") (class "Default")
      (node (ref "J202") (pin "4") (pinfunction "4_4") (pintype "passive"))
      (node (ref "NTC204") (pin "2") (pinfunction "2_2") (pintype "passive"))
    )
    (net (code "75") (name "Net-(J202-Pad5)") (class "Default")
      (node (ref "J202") (pin "5") (pinfunction "5_5") (pintype "passive"))
      (node (ref "NTC205") (pin "1") (pinfunction "2_1") (pintype "passive"))
    )
    (net (code "76") (name "Net-(J202-Pad6)") (class "Default")
      (node (ref "J202") (pin "6") (pinfunction "6_6") (pintype "passive"))
      (node (ref "NTC206") (pin "1") (pinfunction "2_1") (pintype "passive"))
    )
    (net (code "77") (name "Net-(J202-Pad7)") (class "Default")
      (node (ref "J202") (pin "7") (pinfunction "7_7") (pintype "passive"))
      (node (ref "NTC207") (pin "1") (pinfunction "2_1") (pintype "passive"))
    )
    (net (code "78") (name "Net-(J202-Pad8)") (class "Default")
      (node (ref "J202") (pin "8") (pinfunction "8_8") (pintype "passive"))
      (node (ref "NTC208") (pin "1") (pinfunction "2_1") (pintype "passive"))
    )
    (net (code "79") (name "Net-(J302-Pad1)") (class "Default")
      (node (ref "J302") (pin "1") (pinfunction "1_1") (pintype "passive"))
      (node (ref "NTC301") (pin "2") (pinfunction "2_2") (pintype "passive"))
    )
    (net (code "80") (name "Net-(J302-Pad2)") (class "Default")
      (node (ref "J302") (pin "2") (pinfunction "2_2") (pintype "passive"))
      (node (ref "NTC302") (pin "2") (pinfunction "2_2") (pintype "passive"))
    )
    (net (code "81") (name "Net-(J302-Pad3)") (class "Default")
      (node (ref "J302") (pin "3") (pinfunction "3_3") (pintype "passive"))
      (node (ref "NTC303") (pin "2") (pinfunction "2_2") (pintype "passive"))
    )
    (net (code "82") (name "Net-(J302-Pad4)") (class "Default")
      (node (ref "J302") (pin "4") (pinfunction "4_4") (pintype "passive"))
      (node (ref "NTC304") (pin "2") (pinfunction "2_2") (pintype "passive"))
    )
    (net (code "83") (name "Net-(J302-Pad5)") (class "Default")
      (node (ref "J302") (pin "5") (pinfunction "5_5") (pintype "passive"))
      (node (ref "NTC305") (pin "1") (pinfunction "2_1") (pintype "passive"))
    )
    (net (code "84") (name "Net-(J302-Pad6)") (class "Default")
      (node (ref "J302") (pin "6") (pinfunction "6_6") (pintype "passive"))
      (node (ref "NTC306") (pin "1") (pinfunction "2_1") (pintype "passive"))
    )
    (net (code "85") (name "Net-(J302-Pad7)") (class "Default")
      (node (ref "J302") (pin "7") (pinfunction "7_7") (pintype "passive"))
      (node (ref "NTC307") (pin "1") (pinfunction "2_1") (pintype "passive"))
    )
    (net (code "86") (name "Net-(J302-Pad8)") (class "Default")
      (node (ref "J302") (pin "8") (pinfunction "8_8") (pintype "passive"))
      (node (ref "NTC308") (pin "1") (pinfunction "2_1") (pintype "passive"))
    )
  )
)
